# smt.net
KiCad netlist of a schematic drawn in EAGLE
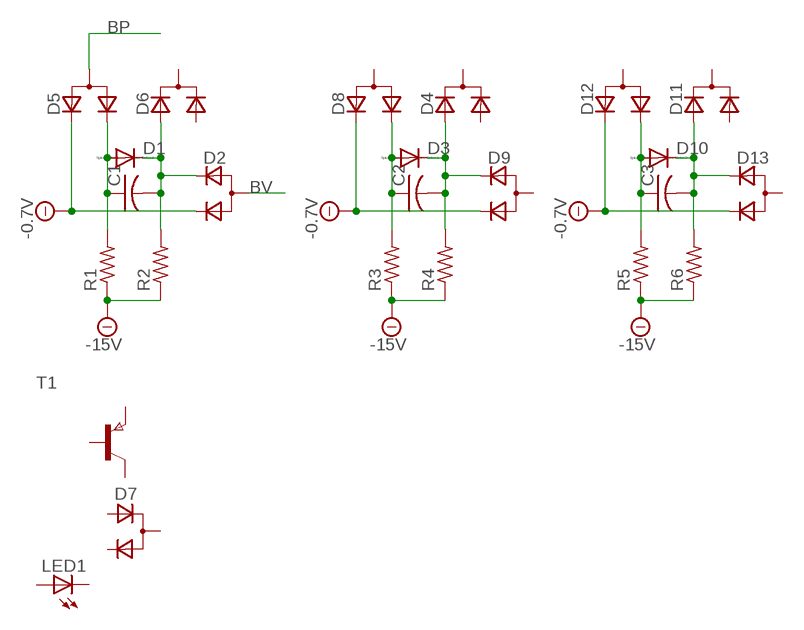
[diagram p0: schematic, sheet 1]

(export (version "E")
  (design (tool "Eeschema 10.0.6"))
  (components
    (comp (ref "C1")
      (value "C-USC0603")
      (footprint "eagle-import:C0603")
      (libsource (lib "eagle-import") (part "C-USC0603"))
    )
    (comp (ref "C2")
      (value "C-USC0603")
      (footprint "eagle-import:C0603")
      (libsource (lib "eagle-import") (part "C-USC0603"))
    )
    (comp (ref "C3")
      (value "C-USC0603")
      (footprint "eagle-import:C0603")
      (libsource (lib "eagle-import") (part "C-USC0603"))
    )
    (comp (ref "D1")
      (value "DIODE-SOD323-R")
      (footprint "eagle-import:SOD323-R")
      (libsource (lib "eagle-import") (part "DIODE-SOD323-R"))
    )
    (comp (ref "D2")
      (value "D_2CSOT323")
      (footprint "eagle-import:SOT323")
      (libsource (lib "eagle-import") (part "D_2CSOT323"))
    )
    (comp (ref "D3")
      (value "DIODE-SOD323-R")
      (footprint "eagle-import:SOD323-R")
      (libsource (lib "eagle-import") (part "DIODE-SOD323-R"))
    )
    (comp (ref "D4")
      (value "D_2ASOT323")
      (footprint "eagle-import:SOT323")
      (libsource (lib "eagle-import") (part "D_2ASOT323"))
    )
    (comp (ref "D5")
      (value "D_2CSOT323")
      (footprint "eagle-import:SOT323")
      (libsource (lib "eagle-import") (part "D_2CSOT323"))
    )
    (comp (ref "D6")
      (value "D_2ASOT323")
      (footprint "eagle-import:SOT323")
      (libsource (lib "eagle-import") (part "D_2ASOT323"))
    )
    (comp (ref "D7")
      (value "D_ACACSOT323")
      (footprint "eagle-import:SOT323")
      (libsource (lib "eagle-import") (part "D_ACACSOT323"))
    )
    (comp (ref "D8")
      (value "D_2CSOT323")
      (footprint "eagle-import:SOT323")
      (libsource (lib "eagle-import") (part "D_2CSOT323"))
    )
    (comp (ref "D9")
      (value "D_2CSOT323")
      (footprint "eagle-import:SOT323")
      (libsource (lib "eagle-import") (part "D_2CSOT323"))
    )
    (comp (ref "D10")
      (value "DIODE-SOD323-R")
      (footprint "eagle-import:SOD323-R")
      (libsource (lib "eagle-import") (part "DIODE-SOD323-R"))
    )
    (comp (ref "D11")
      (value "D_2ASOT323")
      (footprint "eagle-import:SOT323")
      (libsource (lib "eagle-import") (part "D_2ASOT323"))
    )
    (comp (ref "D12")
      (value "D_2CSOT323")
      (footprint "eagle-import:SOT323")
      (libsource (lib "eagle-import") (part "D_2CSOT323"))
    )
    (comp (ref "D13")
      (value "D_2CSOT323")
      (footprint "eagle-import:SOT323")
      (libsource (lib "eagle-import") (part "D_2CSOT323"))
    )
    (comp (ref "LED1")
      (value "LEDCHIPLED_0603")
      (footprint "eagle-import:CHIPLED_0603")
      (libsource (lib "eagle-import") (part "LEDCHIPLED_0603"))
    )
    (comp (ref "R1")
      (value "R-US_R0603")
      (footprint "eagle-import:R0603")
      (libsource (lib "eagle-import") (part "R-US_R0603"))
    )
    (comp (ref "R2")
      (value "R-US_R0603")
      (footprint "eagle-import:R0603")
      (libsource (lib "eagle-import") (part "R-US_R0603"))
    )
    (comp (ref "R3")
      (value "R-US_R0603")
      (footprint "eagle-import:R0603")
      (libsource (lib "eagle-import") (part "R-US_R0603"))
    )
    (comp (ref "R4")
      (value "R-US_R0603")
      (footprint "eagle-import:R0603")
      (libsource (lib "eagle-import") (part "R-US_R0603"))
    )
    (comp (ref "R5")
      (value "R-US_R0603")
      (footprint "eagle-import:R0603")
      (libsource (lib "eagle-import") (part "R-US_R0603"))
    )
    (comp (ref "R6")
      (value "R-US_R0603")
      (footprint "eagle-import:R0603")
      (libsource (lib "eagle-import") (part "R-US_R0603"))
    )
    (comp (ref "T1")
      (value "PNPSOT323")
      (footprint "eagle-import:SOT323")
      (fields (field (name "MPN") "2DB1689-7"))
      (libsource (lib "eagle-import") (part "PNPSOT323"))
    )
  )
  (nets
    (net (code "1") (name "-0.7V") (class "Default")
      (node (ref "D12") (pin "2") (pinfunction "C1_2") (pintype "passive"))
      (node (ref "D13") (pin "3") (pinfunction "C2_3") (pintype "passive"))
      (node (ref "D2") (pin "3") (pinfunction "C2_3") (pintype "passive"))
      (node (ref "D5") (pin "2") (pinfunction "C1_2") (pintype "passive"))
      (node (ref "D8") (pin "2") (pinfunction "C1_2") (pintype "passive"))
      (node (ref "D9") (pin "3") (pinfunction "C2_3") (pintype "passive"))
    )
    (net (code "2") (name "-15V") (class "Default")
      (node (ref "R1") (pin "1") (pinfunction "1_1") (pintype "passive"))
      (node (ref "R2") (pin "1") (pinfunction "1_1") (pintype "passive"))
      (node (ref "R3") (pin "1") (pinfunction "1_1") (pintype "passive"))
      (node (ref "R4") (pin "1") (pinfunction "1_1") (pintype "passive"))
      (node (ref "R5") (pin "1") (pinfunction "1_1") (pintype "passive"))
      (node (ref "R6") (pin "1") (pinfunction "1_1") (pintype "passive"))
    )
    (net (code "3") (name "/BP") (class "Default")
      (node (ref "D5") (pin "1") (pinfunction "A_1") (pintype "passive"))
    )
    (net (code "4") (name "/BV") (class "Default")
      (node (ref "D2") (pin "1") (pinfunction "A_1") (pintype "passive"))
    )
    (net (code "5") (name "Net-(D2-C1)") (class "Default")
      (node (ref "C1") (pin "2") (pinfunction "2_2") (pintype "passive"))
      (node (ref "D1") (pin "C") (pinfunction "C_C") (pintype "passive"))
      (node (ref "D2") (pin "2") (pinfunction "C1_2") (pintype "passive"))
      (node (ref "D6") (pin "2") (pinfunction "A1_2") (pintype "passive"))
      (node (ref "R2") (pin "2") (pinfunction "2_2") (pintype "passive"))
    )
    (net (code "6") (name "Net-(D4-A1)") (class "Default")
      (node (ref "C2") (pin "2") (pinfunction "2_2") (pintype "passive"))
      (node (ref "D3") (pin "C") (pinfunction "C_C") (pintype "passive"))
      (node (ref "D4") (pin "2") (pinfunction "A1_2") (pintype "passive"))
      (node (ref "D9") (pin "2") (pinfunction "C1_2") (pintype "passive"))
      (node (ref "R4") (pin "2") (pinfunction "2_2") (pintype "passive"))
    )
    (net (code "7") (name "Net-(D5-C2)") (class "Default")
      (node (ref "C1") (pin "1") (pinfunction "1_1") (pintype "passive"))
      (node (ref "D1") (pin "A") (pinfunction "A_A") (pintype "passive"))
      (node (ref "D5") (pin "3") (pinfunction "C2_3") (pintype "passive"))
      (node (ref "R1") (pin "2") (pinfunction "2_2") (pintype "passive"))
    )
    (net (code "8") (name "Net-(D8-C2)") (class "Default")
      (node (ref "C2") (pin "1") (pinfunction "1_1") (pintype "passive"))
      (node (ref "D3") (pin "A") (pinfunction "A_A") (pintype "passive"))
      (node (ref "D8") (pin "3") (pinfunction "C2_3") (pintype "passive"))
      (node (ref "R3") (pin "2") (pinfunction "2_2") (pintype "passive"))
    )
    (net (code "9") (name "Net-(D11-A1)") (class "Default")
      (node (ref "C3") (pin "2") (pinfunction "2_2") (pintype "passive"))
      (node (ref "D10") (pin "C") (pinfunction "C_C") (pintype "passive"))
      (node (ref "D11") (pin "2") (pinfunction "A1_2") (pintype "passive"))
      (node (ref "D13") (pin "2") (pinfunction "C1_2") (pintype "passive"))
      (node (ref "R6") (pin "2") (pinfunction "2_2") (pintype "passive"))
    )
    (net (code "10") (name "Net-(D12-C2)") (class "Default")
      (node (ref "C3") (pin "1") (pinfunction "1_1") (pintype "passive"))
      (node (ref "D10") (pin "A") (pinfunction "A_A") (pintype "passive"))
      (node (ref "D12") (pin "3") (pinfunction "C2_3") (pintype "passive"))
      (node (ref "R5") (pin "2") (pinfunction "2_2") (pintype "passive"))
    )
    (net (code "11") (name "unconnected-(D4-A2-Pad3)") (class "Default")
      (node (ref "D4") (pin "3") (pinfunction "A2_3") (pintype "passive"))
    )
    (net (code "12") (name "unconnected-(D4-C-Pad1)") (class "Default")
      (node (ref "D4") (pin "1") (pinfunction "C_1") (pintype "passive"))
    )
    (net (code "13") (name "unconnected-(D6-A2-Pad3)") (class "Default")
      (node (ref "D6") (pin "3") (pinfunction "A2_3") (pintype "passive"))
    )
    (net (code "14") (name "unconnected-(D6-C-Pad1)") (class "Default")
      (node (ref "D6") (pin "1") (pinfunction "C_1") (pintype "passive"))
    )
    (net (code "15") (name "unconnected-(D7-A-Pad3)") (class "Default")
      (node (ref "D7") (pin "3") (pinfunction "A_3") (pintype "passive"))
    )
    (net (code "16") (name "unconnected-(D7-C-Pad2)") (class "Default")
      (node (ref "D7") (pin "2") (pinfunction "C_2") (pintype "passive"))
    )
    (net (code "17") (name "unconnected-(D7-CA-Pad1)") (class "Default")
      (node (ref "D7") (pin "1") (pinfunction "CA_1") (pintype "passive"))
    )
    (net (code "18") (name "unconnected-(D8-A-Pad1)") (class "Default")
      (node (ref "D8") (pin "1") (pinfunction "A_1") (pintype "passive"))
    )
    (net (code "19") (name "unconnected-(D9-A-Pad1)") (class "Default")
      (node (ref "D9") (pin "1") (pinfunction "A_1") (pintype "passive"))
    )
    (net (code "20") (name "unconnected-(D11-A2-Pad3)") (class "Default")
      (node (ref "D11") (pin "3") (pinfunction "A2_3") (pintype "passive"))
    )
    (net (code "21") (name "unconnected-(D11-C-Pad1)") (class "Default")
      (node (ref "D11") (pin "1") (pinfunction "C_1") (pintype "passive"))
    )
    (net (code "22") (name "unconnected-(D12-A-Pad1)") (class "Default")
      (node (ref "D12") (pin "1") (pinfunction "A_1") (pintype "passive"))
    )
    (net (code "23") (name "unconnected-(D13-A-Pad1)") (class "Default")
      (node (ref "D13") (pin "1") (pinfunction "A_1") (pintype "passive"))
    )
    (net (code "24") (name "unconnected-(LED1-PadA)") (class "Default")
      (node (ref "LED1") (pin "A") (pinfunction "A_A") (pintype "passive"))
    )
    (net (code "25") (name "unconnected-(LED1-PadC)") (class "Default")
      (node (ref "LED1") (pin "C") (pinfunction "C_C") (pintype "passive"))
    )
    (net (code "26") (name "unconnected-(T1-B-Pad2)") (class "Default")
      (node (ref "T1") (pin "2") (pinfunction "B_2") (pintype "passive"))
    )
    (net (code "27") (name "unconnected-(T1-C-Pad1)") (class "Default")
      (node (ref "T1") (pin "1") (pinfunction "C_1") (pintype "passive"))
    )
    (net (code "28") (name "unconnected-(T1-E-Pad3)") (class "Default")
      (node (ref "T1") (pin "3") (pinfunction "E_3") (pintype "passive"))
    )
  )
)
